# MotorControllerV1.net
KiCad netlist of a schematic drawn in EAGLE
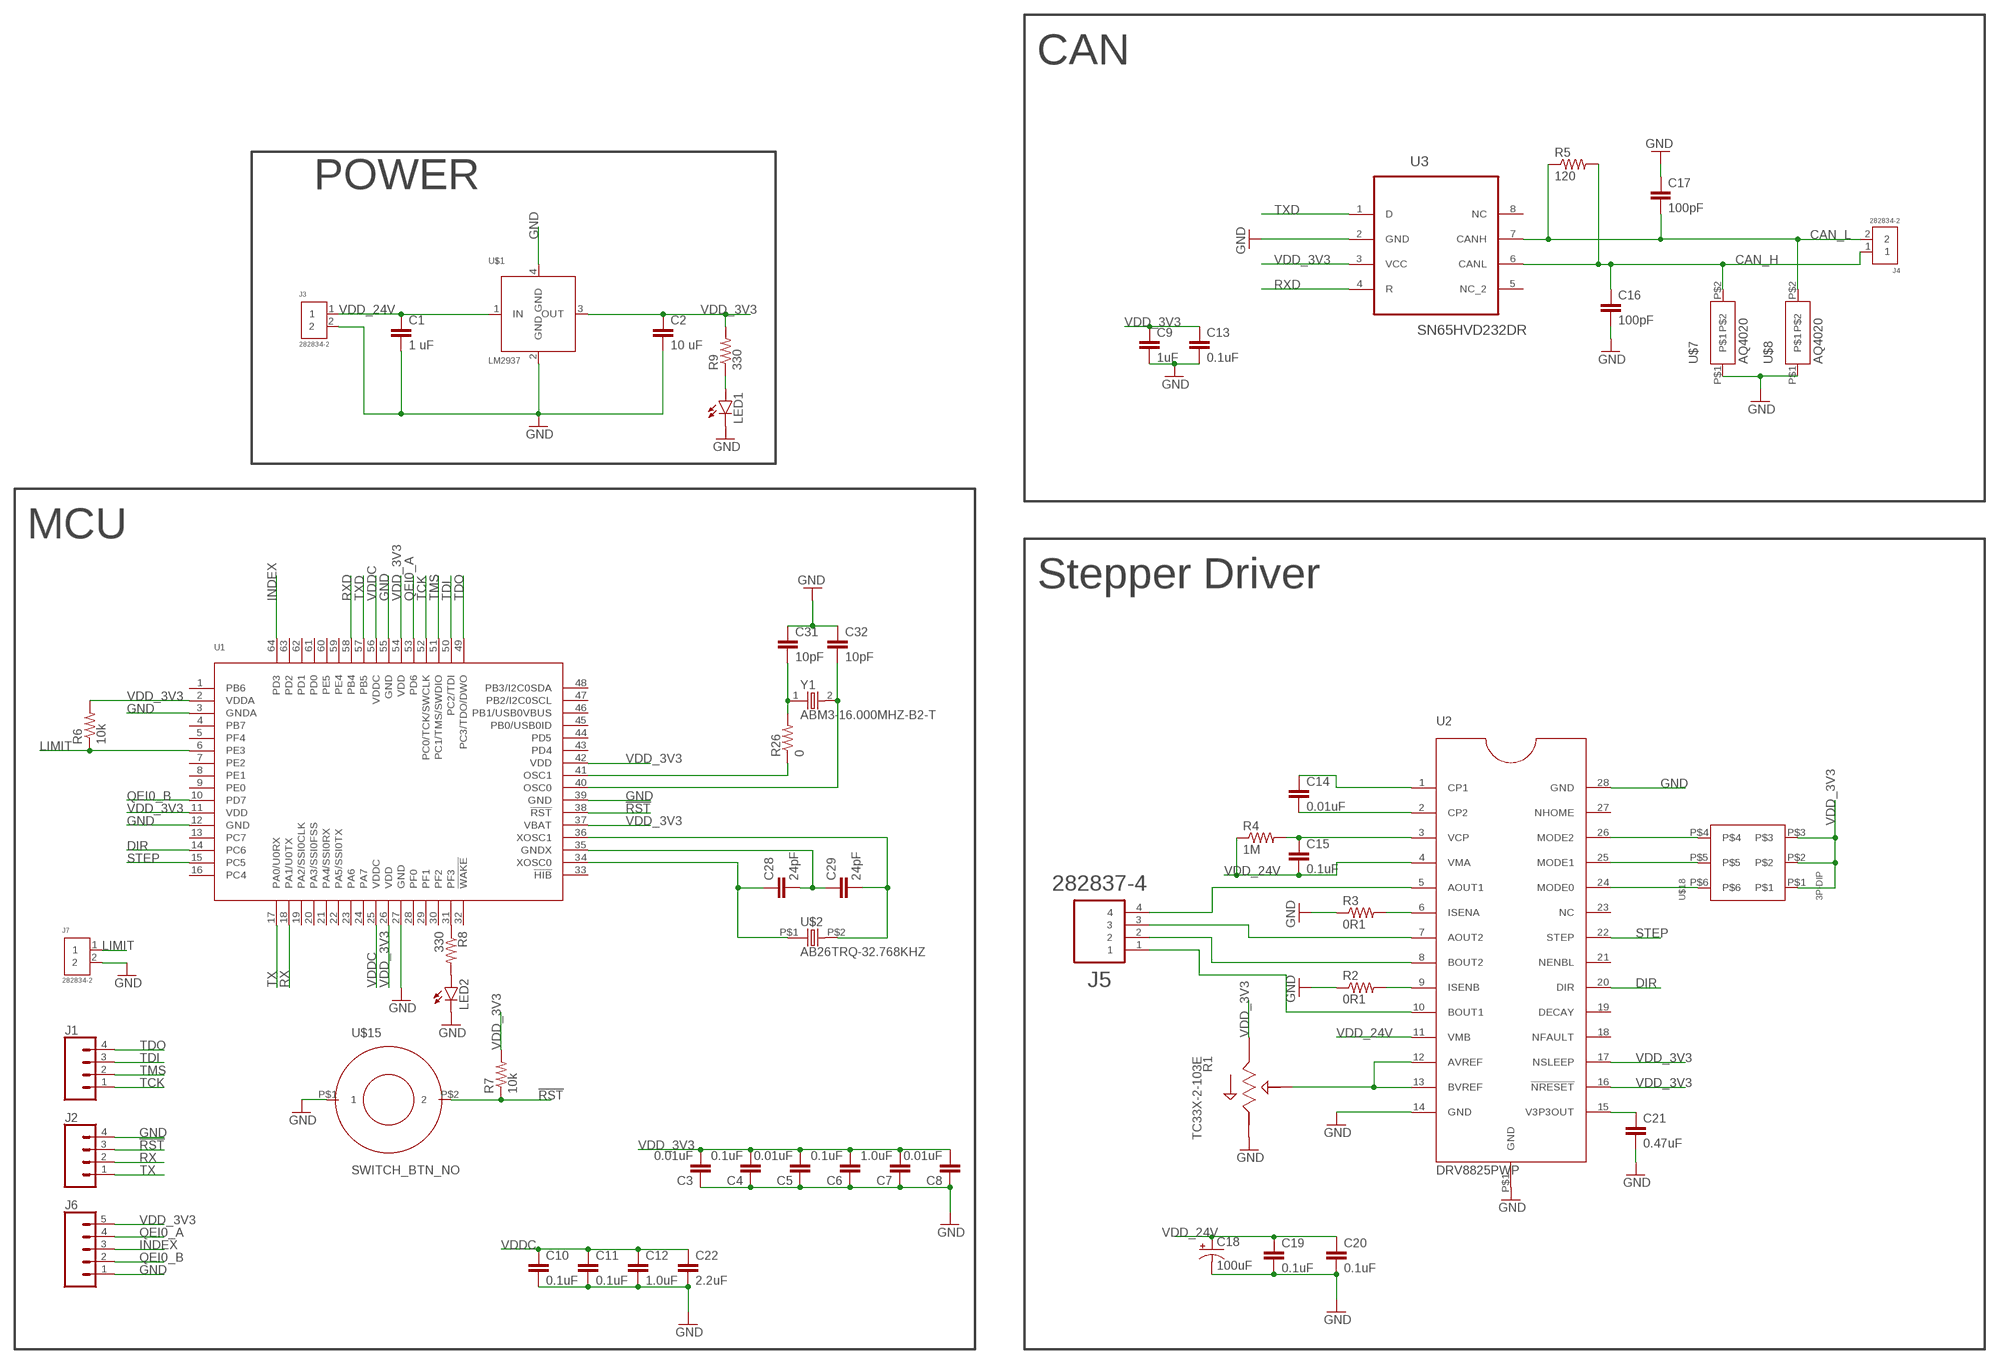
[diagram p0: schematic, sheet 1]

(export (version "E")
  (design (tool "Eeschema 10.0.6"))
  (components
    (comp (ref "C1")
      (value "1 uF")
      (footprint "eagle-import:0805")
      (libsource (lib "eagle-import") (part "CAP"))
    )
    (comp (ref "C2")
      (value "10 uF")
      (footprint "eagle-import:0805")
      (libsource (lib "eagle-import") (part "CAP"))
    )
    (comp (ref "C3")
      (value "0.01uF")
      (footprint "eagle-import:0805")
      (libsource (lib "eagle-import") (part "CAP"))
    )
    (comp (ref "C4")
      (value "0.1uF")
      (footprint "eagle-import:0805")
      (libsource (lib "eagle-import") (part "CAP"))
    )
    (comp (ref "C5")
      (value "0.01uF")
      (footprint "eagle-import:0805")
      (libsource (lib "eagle-import") (part "CAP"))
    )
    (comp (ref "C6")
      (value "0.1uF")
      (footprint "eagle-import:0805")
      (libsource (lib "eagle-import") (part "CAP"))
    )
    (comp (ref "C7")
      (value "1.0uF")
      (footprint "eagle-import:0603")
      (libsource (lib "eagle-import") (part "MicahLBR_CAP"))
    )
    (comp (ref "C8")
      (value "0.01uF")
      (footprint "eagle-import:0805")
      (libsource (lib "eagle-import") (part "CAP"))
    )
    (comp (ref "C9")
      (value "1uF")
      (footprint "eagle-import:0603")
      (libsource (lib "eagle-import") (part "MicahLBR_CAP"))
    )
    (comp (ref "C10")
      (value "0.1uF")
      (footprint "eagle-import:0805")
      (libsource (lib "eagle-import") (part "CAP"))
    )
    (comp (ref "C11")
      (value "0.1uF")
      (footprint "eagle-import:0805")
      (libsource (lib "eagle-import") (part "CAP"))
    )
    (comp (ref "C12")
      (value "1.0uF")
      (footprint "eagle-import:0603")
      (libsource (lib "eagle-import") (part "MicahLBR_CAP"))
    )
    (comp (ref "C13")
      (value "0.1uF")
      (footprint "eagle-import:0805")
      (libsource (lib "eagle-import") (part "CAP"))
    )
    (comp (ref "C14")
      (value "0.01uF")
      (footprint "eagle-import:0805")
      (libsource (lib "eagle-import") (part "CAP"))
    )
    (comp (ref "C15")
      (value "0.1uF")
      (footprint "eagle-import:0805")
      (libsource (lib "eagle-import") (part "CAP"))
    )
    (comp (ref "C16")
      (value "100pF")
      (footprint "eagle-import:0603")
      (libsource (lib "eagle-import") (part "MicahLBR_CAP"))
    )
    (comp (ref "C17")
      (value "100pF")
      (footprint "eagle-import:0603")
      (libsource (lib "eagle-import") (part "MicahLBR_CAP"))
    )
    (comp (ref "C18")
      (value "100uF")
      (footprint "eagle-import:CPOL-RADIAL-3.5MM-8MM")
      (libsource (lib "eagle-import") (part "100UF-POL"))
    )
    (comp (ref "C19")
      (value "0.1uF")
      (footprint "eagle-import:0603")
      (libsource (lib "eagle-import") (part "MicahLBR_CAP"))
    )
    (comp (ref "C20")
      (value "0.1uF")
      (footprint "eagle-import:0603")
      (libsource (lib "eagle-import") (part "MicahLBR_CAP"))
    )
    (comp (ref "C21")
      (value "0.47uF")
      (footprint "eagle-import:0603")
      (libsource (lib "eagle-import") (part "MicahLBR_CAP"))
    )
    (comp (ref "C22")
      (value "2.2uF")
      (footprint "eagle-import:0805")
      (libsource (lib "eagle-import") (part "CAP"))
    )
    (comp (ref "C28")
      (value "24pF")
      (footprint "eagle-import:0805")
      (libsource (lib "eagle-import") (part "CAP"))
    )
    (comp (ref "C29")
      (value "24pF")
      (footprint "eagle-import:0805")
      (libsource (lib "eagle-import") (part "CAP"))
    )
    (comp (ref "C31")
      (value "10pF")
      (footprint "eagle-import:0805")
      (libsource (lib "eagle-import") (part "CAP"))
    )
    (comp (ref "C32")
      (value "10pF")
      (footprint "eagle-import:0805")
      (libsource (lib "eagle-import") (part "CAP"))
    )
    (comp (ref "J1")
      (value "CONN_04")
      (footprint "eagle-import:1X04")
      (libsource (lib "eagle-import") (part "CONN_04"))
    )
    (comp (ref "J2")
      (value "CONN_04")
      (footprint "eagle-import:1X04")
      (libsource (lib "eagle-import") (part "CONN_04"))
    )
    (comp (ref "J3")
      (value "282834-2")
      (footprint "eagle-import:CONN_282834-2")
      (fields (field (name "DIGI-KEY_PART_NUMBER") "A98333-ND") (field (name "MF") "TE Connectivity"))
      (libsource (lib "eagle-import") (part "282834-2"))
    )
    (comp (ref "J4")
      (value "282834-2")
      (footprint "eagle-import:CONN_282834-2")
      (fields (field (name "DIGI-KEY_PART_NUMBER") "A98333-ND") (field (name "MF") "TE Connectivity"))
      (libsource (lib "eagle-import") (part "282834-2"))
    )
    (comp (ref "J5")
      (value "282837-4")
      (footprint "eagle-import:TE_282837-4")
      (fields (field (name "DIGI-KEY_PART_NUMBER") "A124423-ND") (field (name "MF") "TE Connectivity"))
      (libsource (lib "eagle-import") (part "282837-4"))
    )
    (comp (ref "J6")
      (value "CONN_05")
      (footprint "eagle-import:1X05")
      (libsource (lib "eagle-import") (part "CONN_05"))
    )
    (comp (ref "J7")
      (value "282834-2")
      (footprint "eagle-import:CONN_282834-2")
      (fields (field (name "DIGI-KEY_PART_NUMBER") "A98333-ND") (field (name "MF") "TE Connectivity"))
      (libsource (lib "eagle-import") (part "282834-2"))
    )
    (comp (ref "LED1")
      (value "LED0603")
      (footprint "eagle-import:LED-0603")
      (libsource (lib "eagle-import") (part "LED0603"))
    )
    (comp (ref "LED2")
      (value "LED0603")
      (footprint "eagle-import:LED-0603")
      (libsource (lib "eagle-import") (part "LED0603"))
    )
    (comp (ref "R1")
      (value "TC33X-2-103E")
      (footprint "eagle-import:35WR")
      (fields (field (name "DIGI-KEY_PART_NUMBER") "TC33X-103ECT-ND") (field (name "MF") "Bourns"))
      (libsource (lib "eagle-import") (part "TC33X-2-103E"))
    )
    (comp (ref "R2")
      (value "0R1")
      (footprint "eagle-import:0805")
      (libsource (lib "eagle-import") (part "RES"))
    )
    (comp (ref "R3")
      (value "0R1")
      (footprint "eagle-import:0805")
      (libsource (lib "eagle-import") (part "RES"))
    )
    (comp (ref "R4")
      (value "1M")
      (footprint "eagle-import:0603")
      (libsource (lib "eagle-import") (part "MicahLBR_RES"))
    )
    (comp (ref "R5")
      (value "120")
      (footprint "eagle-import:0603")
      (libsource (lib "eagle-import") (part "MicahLBR_RES"))
    )
    (comp (ref "R6")
      (value "10k")
      (footprint "eagle-import:0603")
      (libsource (lib "eagle-import") (part "MicahLBR_RES"))
    )
    (comp (ref "R7")
      (value "10k")
      (footprint "eagle-import:0603")
      (libsource (lib "eagle-import") (part "MicahLBR_RES"))
    )
    (comp (ref "R8")
      (value "330")
      (footprint "eagle-import:0603")
      (libsource (lib "eagle-import") (part "MicahLBR_RES"))
    )
    (comp (ref "R9")
      (value "330")
      (footprint "eagle-import:0603")
      (libsource (lib "eagle-import") (part "MicahLBR_RES"))
    )
    (comp (ref "R26")
      (value "0")
      (footprint "eagle-import:0603")
      (libsource (lib "eagle-import") (part "MicahLBR_RES"))
    )
    (comp (ref "U$1")
      (value "LM2937")
      (footprint "eagle-import:R-PDSO-G4")
      (libsource (lib "eagle-import") (part "LM2937"))
    )
    (comp (ref "U$2")
      (value "AB26TRQ-32.768KHZ")
      (footprint "eagle-import:AB26TRQ")
      (libsource (lib "eagle-import") (part "AB26TRQ-32.768KHZ"))
    )
    (comp (ref "U$7")
      (value "AQ4020")
      (footprint "eagle-import:SOD323")
      (libsource (lib "eagle-import") (part "AQ4020"))
    )
    (comp (ref "U$8")
      (value "AQ4020")
      (footprint "eagle-import:SOD323")
      (libsource (lib "eagle-import") (part "AQ4020"))
    )
    (comp (ref "U$15")
      (value "SWITCH_BTN_NO")
      (footprint "eagle-import:BTN_2")
      (libsource (lib "eagle-import") (part "SWITCH_BTN_NO"))
    )
    (comp (ref "U$18")
      (value "3P-DIP")
      (footprint "eagle-import:CFS-0302MB")
      (libsource (lib "eagle-import") (part "3P-DIP"))
    )
    (comp (ref "U1")
      (value "TM4C123GH6PMI")
      (footprint "eagle-import:QFP50P1200X1200X160-64N")
      (fields (field (name "MF") "Texas Instruments"))
      (libsource (lib "eagle-import") (part "TM4C123GH6PMI"))
    )
    (comp (ref "U2")
      (value "DRV8825PWP")
      (footprint "eagle-import:SOP65P640X120-28N")
      (fields (field (name "MF") "Texas Instruments"))
      (libsource (lib "eagle-import") (part "DRV8825PWP"))
    )
    (comp (ref "U3")
      (value "SN65HVD232DR")
      (footprint "eagle-import:SOIC127P600X175-8N")
      (fields (field (name "MF") "Texas Instruments"))
      (libsource (lib "eagle-import") (part "SN65HVD232DR"))
    )
    (comp (ref "Y1")
      (value "ABM3-16.000MHZ-B2-T")
      (footprint "eagle-import:XTAL500X320X130N")
      (fields (field (name "MF") "Abracon"))
      (libsource (lib "eagle-import") (part "ABM3-16.000MHZ-B2-T"))
    )
  )
  (nets
    (net (code "1") (name "/CAN_H") (class "Default")
      (node (ref "C16") (pin "P$1") (pinfunction "1_P$1") (pintype "passive"))
      (node (ref "J4") (pin "1") (pinfunction "1_1") (pintype "passive"))
      (node (ref "R5") (pin "P$2") (pinfunction "2_P$2") (pintype "passive"))
      (node (ref "U$7") (pin "P$2") (pinfunction "P$2_P$2") (pintype "bidirectional"))
      (node (ref "U3") (pin "6") (pinfunction "CANL_6") (pintype "output"))
    )
    (net (code "2") (name "/CAN_L") (class "Default")
      (node (ref "C17") (pin "P$2") (pinfunction "2_P$2") (pintype "passive"))
      (node (ref "J4") (pin "2") (pinfunction "2_2") (pintype "passive"))
      (node (ref "R5") (pin "P$1") (pinfunction "1_P$1") (pintype "passive"))
      (node (ref "U$8") (pin "P$2") (pinfunction "P$2_P$2") (pintype "bidirectional"))
      (node (ref "U3") (pin "7") (pinfunction "CANH_7") (pintype "output"))
    )
    (net (code "3") (name "/DIR") (class "Default")
      (node (ref "U1") (pin "14") (pinfunction "PC6_14") (pintype "bidirectional"))
      (node (ref "U2") (pin "20") (pinfunction "DIR_20") (pintype "input"))
    )
    (net (code "4") (name "/INDEX") (class "Default")
      (node (ref "J6") (pin "3") (pinfunction "3_3") (pintype "passive"))
      (node (ref "U1") (pin "64") (pinfunction "PD3_64") (pintype "bidirectional"))
    )
    (net (code "5") (name "/LIMIT") (class "Default")
      (node (ref "J7") (pin "1") (pinfunction "1_1") (pintype "passive"))
      (node (ref "R6") (pin "P$1") (pinfunction "1_P$1") (pintype "passive"))
      (node (ref "U1") (pin "6") (pinfunction "PE3_6") (pintype "bidirectional"))
    )
    (net (code "6") (name "/QEI0_A") (class "Default")
      (node (ref "J6") (pin "4") (pinfunction "4_4") (pintype "passive"))
      (node (ref "U1") (pin "53") (pinfunction "PD6_53") (pintype "bidirectional"))
    )
    (net (code "7") (name "/QEI0_B") (class "Default")
      (node (ref "J6") (pin "2") (pinfunction "2_2") (pintype "passive"))
      (node (ref "U1") (pin "10") (pinfunction "PD7_10") (pintype "bidirectional"))
    )
    (net (code "8") (name "/RX") (class "Default")
      (node (ref "J2") (pin "2") (pinfunction "2_2") (pintype "passive"))
      (node (ref "U1") (pin "18") (pinfunction "PA1/U0TX_18") (pintype "bidirectional"))
    )
    (net (code "9") (name "/RXD") (class "Default")
      (node (ref "U1") (pin "58") (pinfunction "PB4_58") (pintype "bidirectional"))
      (node (ref "U3") (pin "4") (pinfunction "R_4") (pintype "output"))
    )
    (net (code "10") (name "/STEP") (class "Default")
      (node (ref "U1") (pin "15") (pinfunction "PC5_15") (pintype "bidirectional"))
      (node (ref "U2") (pin "22") (pinfunction "STEP_22") (pintype "input"))
    )
    (net (code "11") (name "/TCK") (class "Default")
      (node (ref "J1") (pin "1") (pinfunction "1_1") (pintype "passive"))
      (node (ref "U1") (pin "52") (pinfunction "PC0/TCK/SWCLK_52") (pintype "bidirectional"))
    )
    (net (code "12") (name "/TDI") (class "Default")
      (node (ref "J1") (pin "3") (pinfunction "3_3") (pintype "passive"))
      (node (ref "U1") (pin "50") (pinfunction "PC2/TDI_50") (pintype "bidirectional"))
    )
    (net (code "13") (name "/TDO") (class "Default")
      (node (ref "J1") (pin "4") (pinfunction "4_4") (pintype "passive"))
      (node (ref "U1") (pin "49") (pinfunction "PC3/TDO/DWO_49") (pintype "bidirectional"))
    )
    (net (code "14") (name "/TMS") (class "Default")
      (node (ref "J1") (pin "2") (pinfunction "2_2") (pintype "passive"))
      (node (ref "U1") (pin "51") (pinfunction "PC1/TMS/SWDIO_51") (pintype "bidirectional"))
    )
    (net (code "15") (name "/TX") (class "Default")
      (node (ref "J2") (pin "1") (pinfunction "1_1") (pintype "passive"))
      (node (ref "U1") (pin "17") (pinfunction "PA0/U0RX_17") (pintype "bidirectional"))
    )
    (net (code "16") (name "/TXD") (class "Default")
      (node (ref "U1") (pin "57") (pinfunction "PB5_57") (pintype "bidirectional"))
      (node (ref "U3") (pin "1") (pinfunction "D_1") (pintype "input"))
    )
    (net (code "17") (name "/VDDC") (class "Default")
      (node (ref "C10") (pin "1") (pinfunction "1_1") (pintype "passive"))
      (node (ref "C11") (pin "1") (pinfunction "1_1") (pintype "passive"))
      (node (ref "C12") (pin "P$1") (pinfunction "1_P$1") (pintype "passive"))
      (node (ref "C22") (pin "1") (pinfunction "1_1") (pintype "passive"))
      (node (ref "U1") (pin "25") (pinfunction "VDDC_25") (pintype "power_in"))
      (node (ref "U1") (pin "56") (pinfunction "VDDC_56") (pintype "power_in"))
    )
    (net (code "18") (name "/VDD_3V3") (class "Default")
      (node (ref "C13") (pin "1") (pinfunction "1_1") (pintype "passive"))
      (node (ref "C2") (pin "1") (pinfunction "1_1") (pintype "passive"))
      (node (ref "C3") (pin "2") (pinfunction "2_2") (pintype "passive"))
      (node (ref "C4") (pin "2") (pinfunction "2_2") (pintype "passive"))
      (node (ref "C5") (pin "2") (pinfunction "2_2") (pintype "passive"))
      (node (ref "C6") (pin "2") (pinfunction "2_2") (pintype "passive"))
      (node (ref "C7") (pin "P$2") (pinfunction "2_P$2") (pintype "passive"))
      (node (ref "C8") (pin "2") (pinfunction "2_2") (pintype "passive"))
      (node (ref "C9") (pin "P$1") (pinfunction "1_P$1") (pintype "passive"))
      (node (ref "J6") (pin "5") (pinfunction "5_5") (pintype "passive"))
      (node (ref "R1") (pin "1") (pinfunction "1_1") (pintype "passive"))
      (node (ref "R6") (pin "P$2") (pinfunction "2_P$2") (pintype "passive"))
      (node (ref "R7") (pin "P$2") (pinfunction "2_P$2") (pintype "passive"))
      (node (ref "R9") (pin "P$2") (pinfunction "2_P$2") (pintype "passive"))
      (node (ref "U$1") (pin "3") (pinfunction "OUT_3") (pintype "bidirectional"))
      (node (ref "U$18") (pin "P$1") (pinfunction "P$1_P$1") (pintype "bidirectional"))
      (node (ref "U$18") (pin "P$2") (pinfunction "P$2_P$2") (pintype "bidirectional"))
      (node (ref "U$18") (pin "P$3") (pinfunction "P$3_P$3") (pintype "bidirectional"))
      (node (ref "U1") (pin "11") (pinfunction "VDD_11") (pintype "power_in"))
      (node (ref "U1") (pin "2") (pinfunction "VDDA_2") (pintype "power_in"))
      (node (ref "U1") (pin "26") (pinfunction "VDD_26") (pintype "power_in"))
      (node (ref "U1") (pin "37") (pinfunction "VBAT_37") (pintype "power_in"))
      (node (ref "U1") (pin "42") (pinfunction "VDD_42") (pintype "power_in"))
      (node (ref "U1") (pin "54") (pinfunction "VDD_54") (pintype "power_in"))
      (node (ref "U2") (pin "16") (pinfunction "~{NRESET}_16") (pintype "input"))
      (node (ref "U2") (pin "17") (pinfunction "NSLEEP_17") (pintype "input"))
      (node (ref "U3") (pin "3") (pinfunction "VCC_3") (pintype "power_in"))
    )
    (net (code "19") (name "/VDD_24V") (class "Default")
      (node (ref "C1") (pin "1") (pinfunction "1_1") (pintype "passive"))
      (node (ref "C15") (pin "2") (pinfunction "2_2") (pintype "passive"))
      (node (ref "C18") (pin "1") (pinfunction "+_1") (pintype "passive"))
      (node (ref "C19") (pin "P$1") (pinfunction "1_P$1") (pintype "passive"))
      (node (ref "C20") (pin "P$1") (pinfunction "1_P$1") (pintype "passive"))
      (node (ref "J3") (pin "1") (pinfunction "1_1") (pintype "passive"))
      (node (ref "R4") (pin "P$1") (pinfunction "1_P$1") (pintype "passive"))
      (node (ref "U$1") (pin "1") (pinfunction "IN_1") (pintype "bidirectional"))
      (node (ref "U2") (pin "11") (pinfunction "VMB_11") (pintype "power_in"))
      (node (ref "U2") (pin "4") (pinfunction "VMA_4") (pintype "power_in"))
    )
    (net (code "20") (name "/~{RST}") (class "Default")
      (node (ref "J2") (pin "3") (pinfunction "3_3") (pintype "passive"))
      (node (ref "R7") (pin "P$1") (pinfunction "1_P$1") (pintype "passive"))
      (node (ref "U$15") (pin "P$2") (pinfunction "2_P$2") (pintype "bidirectional"))
      (node (ref "U1") (pin "38") (pinfunction "~{RST}_38") (pintype "input"))
    )
    (net (code "21") (name "GND") (class "Default")
      (node (ref "C1") (pin "2") (pinfunction "2_2") (pintype "passive"))
      (node (ref "C10") (pin "2") (pinfunction "2_2") (pintype "passive"))
      (node (ref "C11") (pin "2") (pinfunction "2_2") (pintype "passive"))
      (node (ref "C12") (pin "P$2") (pinfunction "2_P$2") (pintype "passive"))
      (node (ref "C13") (pin "2") (pinfunction "2_2") (pintype "passive"))
      (node (ref "C16") (pin "P$2") (pinfunction "2_P$2") (pintype "passive"))
      (node (ref "C17") (pin "P$1") (pinfunction "1_P$1") (pintype "passive"))
      (node (ref "C18") (pin "2") (pinfunction "-_2") (pintype "passive"))
      (node (ref "C19") (pin "P$2") (pinfunction "2_P$2") (pintype "passive"))
      (node (ref "C2") (pin "2") (pinfunction "2_2") (pintype "passive"))
      (node (ref "C20") (pin "P$2") (pinfunction "2_P$2") (pintype "passive"))
      (node (ref "C21") (pin "P$2") (pinfunction "2_P$2") (pintype "passive"))
      (node (ref "C22") (pin "2") (pinfunction "2_2") (pintype "passive"))
      (node (ref "C3") (pin "1") (pinfunction "1_1") (pintype "passive"))
      (node (ref "C31") (pin "1") (pinfunction "1_1") (pintype "passive"))
      (node (ref "C32") (pin "1") (pinfunction "1_1") (pintype "passive"))
      (node (ref "C4") (pin "1") (pinfunction "1_1") (pintype "passive"))
      (node (ref "C5") (pin "1") (pinfunction "1_1") (pintype "passive"))
      (node (ref "C6") (pin "1") (pinfunction "1_1") (pintype "passive"))
      (node (ref "C7") (pin "P$1") (pinfunction "1_P$1") (pintype "passive"))
      (node (ref "C8") (pin "1") (pinfunction "1_1") (pintype "passive"))
      (node (ref "C9") (pin "P$2") (pinfunction "2_P$2") (pintype "passive"))
      (node (ref "J2") (pin "4") (pinfunction "4_4") (pintype "passive"))
      (node (ref "J3") (pin "2") (pinfunction "2_2") (pintype "passive"))
      (node (ref "J6") (pin "1") (pinfunction "1_1") (pintype "passive"))
      (node (ref "J7") (pin "2") (pinfunction "2_2") (pintype "passive"))
      (node (ref "LED1") (pin "C") (pinfunction "C_C") (pintype "passive"))
      (node (ref "LED2") (pin "C") (pinfunction "C_C") (pintype "passive"))
      (node (ref "R1") (pin "3") (pinfunction "3_3") (pintype "passive"))
      (node (ref "R2") (pin "1") (pinfunction "1_1") (pintype "passive"))
      (node (ref "R3") (pin "1") (pinfunction "1_1") (pintype "passive"))
      (node (ref "U$1") (pin "2") (pinfunction "GND_2") (pintype "bidirectional"))
      (node (ref "U$1") (pin "4") (pinfunction "GND_4") (pintype "bidirectional"))
      (node (ref "U$15") (pin "P$1") (pinfunction "1_P$1") (pintype "bidirectional"))
      (node (ref "U$7") (pin "P$1") (pinfunction "P$1_P$1") (pintype "bidirectional"))
      (node (ref "U$8") (pin "P$1") (pinfunction "P$1_P$1") (pintype "bidirectional"))
      (node (ref "U1") (pin "12") (pinfunction "GND_12") (pintype "power_in"))
      (node (ref "U1") (pin "27") (pinfunction "GND_27") (pintype "power_in"))
      (node (ref "U1") (pin "3") (pinfunction "GNDA_3") (pintype "power_in"))
      (node (ref "U1") (pin "39") (pinfunction "GND_39") (pintype "power_in"))
      (node (ref "U1") (pin "55") (pinfunction "GND_55") (pintype "power_in"))
      (node (ref "U2") (pin "14") (pinfunction "GND_14") (pintype "passive"))
      (node (ref "U2") (pin "28") (pinfunction "GND_28") (pintype "passive"))
      (node (ref "U2") (pin "P$1") (pinfunction "GND_P$1") (pintype "bidirectional"))
      (node (ref "U3") (pin "2") (pinfunction "GND_2") (pintype "passive"))
    )
    (net (code "22") (name "Net-(C21-1)") (class "Default")
      (node (ref "C21") (pin "P$1") (pinfunction "1_P$1") (pintype "passive"))
      (node (ref "U2") (pin "15") (pinfunction "V3P3OUT_15") (pintype "output"))
    )
    (net (code "23") (name "Net-(R4-2)") (class "Default")
      (node (ref "C15") (pin "1") (pinfunction "1_1") (pintype "passive"))
      (node (ref "R4") (pin "P$2") (pinfunction "2_P$2") (pintype "passive"))
      (node (ref "U2") (pin "3") (pinfunction "VCP_3") (pintype "bidirectional"))
    )
    (net (code "24") (name "Net-(R8-1)") (class "Default")
      (node (ref "R8") (pin "P$1") (pinfunction "1_P$1") (pintype "passive"))
      (node (ref "U1") (pin "31") (pinfunction "PF3_31") (pintype "bidirectional"))
    )
    (net (code "25") (name "Net-(R8-2)") (class "Default")
      (node (ref "LED2") (pin "A") (pinfunction "A_A") (pintype "passive"))
      (node (ref "R8") (pin "P$2") (pinfunction "2_P$2") (pintype "passive"))
    )
    (net (code "26") (name "Net-(R9-1)") (class "Default")
      (node (ref "LED1") (pin "A") (pinfunction "A_A") (pintype "passive"))
      (node (ref "R9") (pin "P$1") (pinfunction "1_P$1") (pintype "passive"))
    )
    (net (code "27") (name "Net-(R26-1)") (class "Default")
      (node (ref "R26") (pin "P$1") (pinfunction "1_P$1") (pintype "passive"))
      (node (ref "U1") (pin "41") (pinfunction "OSC1_41") (pintype "output"))
    )
    (net (code "28") (name "Net-(R26-2)") (class "Default")
      (node (ref "C31") (pin "2") (pinfunction "2_2") (pintype "passive"))
      (node (ref "R26") (pin "P$2") (pinfunction "2_P$2") (pintype "passive"))
      (node (ref "Y1") (pin "1") (pinfunction "1_1") (pintype "passive"))
    )
    (net (code "29") (name "Net-(U$2-1)") (class "Default")
      (node (ref "C28") (pin "1") (pinfunction "1_1") (pintype "passive"))
      (node (ref "U$2") (pin "P$1") (pinfunction "1_P$1") (pintype "passive"))
      (node (ref "U1") (pin "34") (pinfunction "XOSC0_34") (pintype "input"))
    )
    (net (code "30") (name "Net-(U$2-2)") (class "Default")
      (node (ref "C29") (pin "2") (pinfunction "2_2") (pintype "passive"))
      (node (ref "U$2") (pin "P$2") (pinfunction "2_P$2") (pintype "passive"))
      (node (ref "U1") (pin "36") (pinfunction "XOSC1_36") (pintype "output"))
    )
    (net (code "31") (name "Net-(U1-GNDX)") (class "Default")
      (node (ref "C28") (pin "2") (pinfunction "2_2") (pintype "passive"))
      (node (ref "C29") (pin "1") (pinfunction "1_1") (pintype "passive"))
      (node (ref "U1") (pin "35") (pinfunction "GNDX_35") (pintype "power_in"))
    )
    (net (code "32") (name "Net-(U1-OSC0)") (class "Default")
      (node (ref "C32") (pin "2") (pinfunction "2_2") (pintype "passive"))
      (node (ref "U1") (pin "40") (pinfunction "OSC0_40") (pintype "input"))
      (node (ref "Y1") (pin "2") (pinfunction "2_2") (pintype "passive"))
    )
    (net (code "33") (name "Net-(U2-AOUT1)") (class "Default")
      (node (ref "J5") (pin "4") (pinfunction "4_4") (pintype "passive"))
      (node (ref "U2") (pin "5") (pinfunction "AOUT1_5") (pintype "output"))
    )
    (net (code "34") (name "Net-(U2-AOUT2)") (class "Default")
      (node (ref "J5") (pin "3") (pinfunction "3_3") (pintype "passive"))
      (node (ref "U2") (pin "7") (pinfunction "AOUT2_7") (pintype "output"))
    )
    (net (code "35") (name "Net-(U2-AVREF)") (class "Default")
      (node (ref "R1") (pin "2") (pinfunction "2_2") (pintype "passive"))
      (node (ref "U2") (pin "12") (pinfunction "AVREF_12") (pintype "input"))
      (node (ref "U2") (pin "13") (pinfunction "BVREF_13") (pintype "input"))
    )
    (net (code "36") (name "Net-(U2-BOUT1)") (class "Default")
      (node (ref "J5") (pin "1") (pinfunction "1_1") (pintype "passive"))
      (node (ref "U2") (pin "10") (pinfunction "BOUT1_10") (pintype "output"))
    )
    (net (code "37") (name "Net-(U2-BOUT2)") (class "Default")
      (node (ref "J5") (pin "2") (pinfunction "2_2") (pintype "passive"))
      (node (ref "U2") (pin "8") (pinfunction "BOUT2_8") (pintype "output"))
    )
    (net (code "38") (name "Net-(U2-CP1)") (class "Default")
      (node (ref "C14") (pin "1") (pinfunction "1_1") (pintype "passive"))
      (node (ref "U2") (pin "1") (pinfunction "CP1_1") (pintype "bidirectional"))
    )
    (net (code "39") (name "Net-(U2-CP2)") (class "Default")
      (node (ref "C14") (pin "2") (pinfunction "2_2") (pintype "passive"))
      (node (ref "U2") (pin "2") (pinfunction "CP2_2") (pintype "bidirectional"))
    )
    (net (code "40") (name "Net-(U2-ISENA)") (class "Default")
      (node (ref "R3") (pin "2") (pinfunction "2_2") (pintype "passive"))
      (node (ref "U2") (pin "6") (pinfunction "ISENA_6") (pintype "bidirectional"))
    )
    (net (code "41") (name "Net-(U2-ISENB)") (class "Default")
      (node (ref "R2") (pin "2") (pinfunction "2_2") (pintype "passive"))
      (node (ref "U2") (pin "9") (pinfunction "ISENB_9") (pintype "bidirectional"))
    )
    (net (code "42") (name "Net-(U2-MODE0)") (class "Default")
      (node (ref "U$18") (pin "P$6") (pinfunction "P$6_P$6") (pintype "bidirectional"))
      (node (ref "U2") (pin "24") (pinfunction "MODE0_24") (pintype "input"))
    )
    (net (code "43") (name "Net-(U2-MODE1)") (class "Default")
      (node (ref "U$18") (pin "P$5") (pinfunction "P$5_P$5") (pintype "bidirectional"))
      (node (ref "U2") (pin "25") (pinfunction "MODE1_25") (pintype "input"))
    )
    (net (code "44") (name "Net-(U2-MODE2)") (class "Default")
      (node (ref "U$18") (pin "P$4") (pinfunction "P$4_P$4") (pintype "bidirectional"))
      (node (ref "U2") (pin "26") (pinfunction "MODE2_26") (pintype "input"))
    )
    (net (code "45") (name "unconnected-(U1-PA2{slash}SSI0CLK-Pad19)") (class "Default")
      (node (ref "U1") (pin "19") (pinfunction "PA2/SSI0CLK_19") (pintype "bidirectional"))
    )
    (net (code "46") (name "unconnected-(U1-PA3{slash}SSI0FSS-Pad20)") (class "Default")
      (node (ref "U1") (pin "20") (pinfunction "PA3/SSI0FSS_20") (pintype "bidirectional"))
    )
    (net (code "47") (name "unconnected-(U1-PA4{slash}SSI0RX-Pad21)") (class "Default")
      (node (ref "U1") (pin "21") (pinfunction "PA4/SSI0RX_21") (pintype "bidirectional"))
    )
    (net (code "48") (name "unconnected-(U1-PA5{slash}SSI0TX-Pad22)") (class "Default")
      (node (ref "U1") (pin "22") (pinfunction "PA5/SSI0TX_22") (pintype "bidirectional"))
    )
    (net (code "49") (name "unconnected-(U1-PA6-Pad23)") (class "Default")
      (node (ref "U1") (pin "23") (pinfunction "PA6_23") (pintype "bidirectional"))
    )
    (net (code "50") (name "unconnected-(U1-PA7-Pad24)") (class "Default")
      (node (ref "U1") (pin "24") (pinfunction "PA7_24") (pintype "bidirectional"))
    )
    (net (code "51") (name "unconnected-(U1-PB0{slash}USB0ID-Pad45)") (class "Default")
      (node (ref "U1") (pin "45") (pinfunction "PB0/USB0ID_45") (pintype "bidirectional"))
    )
    (net (code "52") (name "unconnected-(U1-PB1{slash}USB0VBUS-Pad46)") (class "Default")
      (node (ref "U1") (pin "46") (pinfunction "PB1/USB0VBUS_46") (pintype "bidirectional"))
    )
    (net (code "53") (name "unconnected-(U1-PB2{slash}I2C0SCL-Pad47)") (class "Default")
      (node (ref "U1") (pin "47") (pinfunction "PB2/I2C0SCL_47") (pintype "bidirectional"))
    )
    (net (code "54") (name "unconnected-(U1-PB3{slash}I2C0SDA-Pad48)") (class "Default")
      (node (ref "U1") (pin "48") (pinfunction "PB3/I2C0SDA_48") (pintype "bidirectional"))
    )
    (net (code "55") (name "unconnected-(U1-PB6-Pad1)") (class "Default")
      (node (ref "U1") (pin "1") (pinfunction "PB6_1") (pintype "bidirectional"))
    )
    (net (code "56") (name "unconnected-(U1-PB7-Pad4)") (class "Default")
      (node (ref "U1") (pin "4") (pinfunction "PB7_4") (pintype "bidirectional"))
    )
    (net (code "57") (name "unconnected-(U1-PC4-Pad16)") (class "Default")
      (node (ref "U1") (pin "16") (pinfunction "PC4_16") (pintype "bidirectional"))
    )
    (net (code "58") (name "unconnected-(U1-PC7-Pad13)") (class "Default")
      (node (ref "U1") (pin "13") (pinfunction "PC7_13") (pintype "bidirectional"))
    )
    (net (code "59") (name "unconnected-(U1-PD0-Pad61)") (class "Default")
      (node (ref "U1") (pin "61") (pinfunction "PD0_61") (pintype "bidirectional"))
    )
    (net (code "60") (name "unconnected-(U1-PD1-Pad62)") (class "Default")
      (node (ref "U1") (pin "62") (pinfunction "PD1_62") (pintype "bidirectional"))
    )
    (net (code "61") (name "unconnected-(U1-PD2-Pad63)") (class "Default")
      (node (ref "U1") (pin "63") (pinfunction "PD2_63") (pintype "bidirectional"))
    )
    (net (code "62") (name "unconnected-(U1-PD4-Pad43)") (class "Default")
      (node (ref "U1") (pin "43") (pinfunction "PD4_43") (pintype "bidirectional"))
    )
    (net (code "63") (name "unconnected-(U1-PD5-Pad44)") (class "Default")
      (node (ref "U1") (pin "44") (pinfunction "PD5_44") (pintype "bidirectional"))
    )
    (net (code "64") (name "unconnected-(U1-PE0-Pad9)") (class "Default")
      (node (ref "U1") (pin "9") (pinfunction "PE0_9") (pintype "bidirectional"))
    )
    (net (code "65") (name "unconnected-(U1-PE1-Pad8)") (class "Default")
      (node (ref "U1") (pin "8") (pinfunction "PE1_8") (pintype "bidirectional"))
    )
    (net (code "66") (name "unconnected-(U1-PE2-Pad7)") (class "Default")
      (node (ref "U1") (pin "7") (pinfunction "PE2_7") (pintype "bidirectional"))
    )
    (net (code "67") (name "unconnected-(U1-PE4-Pad59)") (class "Default")
      (node (ref "U1") (pin "59") (pinfunction "PE4_59") (pintype "bidirectional"))
    )
    (net (code "68") (name "unconnected-(U1-PE5-Pad60)") (class "Default")
      (node (ref "U1") (pin "60") (pinfunction "PE5_60") (pintype "bidirectional"))
    )
    (net (code "69") (name "unconnected-(U1-PF0-Pad28)") (class "Default")
      (node (ref "U1") (pin "28") (pinfunction "PF0_28") (pintype "bidirectional"))
    )
    (net (code "70") (name "unconnected-(U1-PF1-Pad29)") (class "Default")
      (node (ref "U1") (pin "29") (pinfunction "PF1_29") (pintype "bidirectional"))
    )
    (net (code "71") (name "unconnected-(U1-PF2-Pad30)") (class "Default")
      (node (ref "U1") (pin "30") (pinfunction "PF2_30") (pintype "bidirectional"))
    )
    (net (code "72") (name "unconnected-(U1-PF4-Pad5)") (class "Default")
      (node (ref "U1") (pin "5") (pinfunction "PF4_5") (pintype "bidirectional"))
    )
    (net (code "73") (name "unconnected-(U1-~{HIB}-Pad33)") (class "Default")
      (node (ref "U1") (pin "33") (pinfunction "~{HIB}_33") (pintype "output"))
    )
    (net (code "74") (name "unconnected-(U1-~{WAKE}-Pad32)") (class "Default")
      (node (ref "U1") (pin "32") (pinfunction "~{WAKE}_32") (pintype "input"))
    )
    (net (code "75") (name "unconnected-(U2-DECAY-Pad19)") (class "Default")
      (node (ref "U2") (pin "19") (pinfunction "DECAY_19") (pintype "input"))
    )
    (net (code "76") (name "unconnected-(U2-NC-Pad23)") (class "Default")
      (node (ref "U2") (pin "23") (pinfunction "NC_23") (pintype "bidirectional"))
    )
    (net (code "77") (name "unconnected-(U2-NENBL-Pad21)") (class "Default")
      (node (ref "U2") (pin "21") (pinfunction "NENBL_21") (pintype "input"))
    )
    (net (code "78") (name "unconnected-(U2-NFAULT-Pad18)") (class "Default")
      (node (ref "U2") (pin "18") (pinfunction "NFAULT_18") (pintype "output"))
    )
    (net (code "79") (name "unconnected-(U2-NHOME-Pad27)") (class "Default")
      (node (ref "U2") (pin "27") (pinfunction "NHOME_27") (pintype "output"))
    )
    (net (code "80") (name "unconnected-(U3-NC-Pad8)") (class "Default")
      (node (ref "U3") (pin "8") (pinfunction "NC_8") (pintype "no_connect"))
    )
    (net (code "81") (name "unconnected-(U3-NC_2-Pad5)") (class "Default")
      (node (ref "U3") (pin "5") (pinfunction "NC_2_5") (pintype "no_connect"))
    )
  )
)
